# Mega_Shield-v13.net
KiCad netlist of a schematic drawn in EAGLE
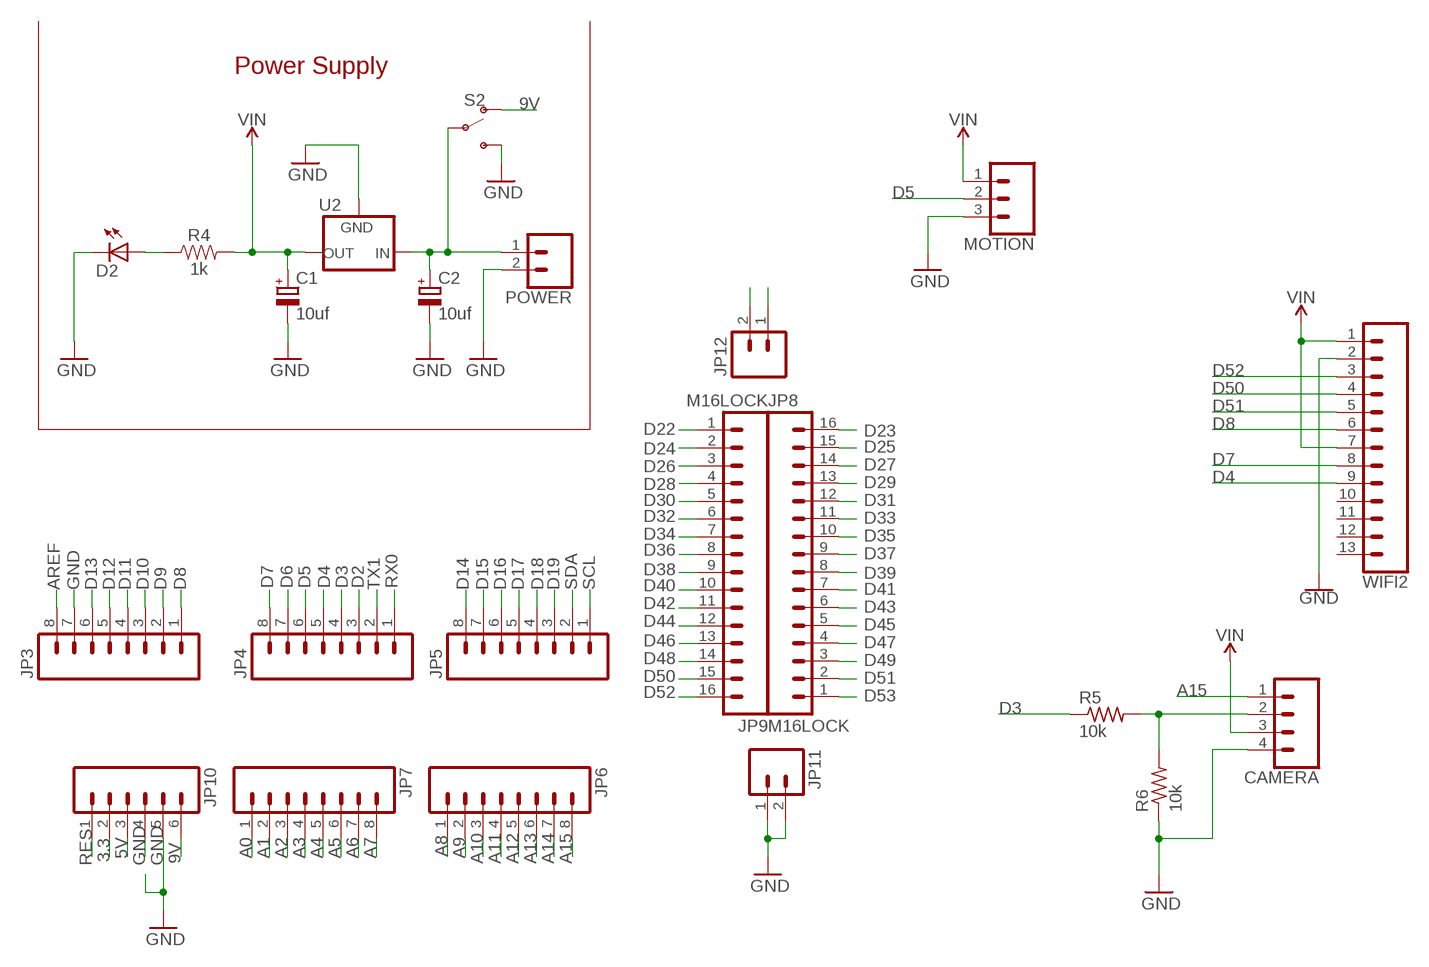
[diagram p0: schematic, sheet 1]

(export (version "E")
  (design (tool "Eeschema 10.0.6"))
  (components
    (comp (ref "C1")
      (value "10uf")
      (footprint "eagle-import:E2,5-6")
      (libsource (lib "eagle-import") (part "CPOL-EUE2.5-6"))
    )
    (comp (ref "C2")
      (value "10uf")
      (footprint "eagle-import:E2,5-6")
      (libsource (lib "eagle-import") (part "CPOL-EUE2.5-6"))
    )
    (comp (ref "CAMERA")
      (value "CONN_04")
      (footprint "eagle-import:1X04")
      (libsource (lib "eagle-import") (part "CONN_04"))
    )
    (comp (ref "D2")
      (value "LED3MM")
      (footprint "eagle-import:LED3MM")
      (libsource (lib "eagle-import") (part "LED3MM"))
    )
    (comp (ref "JP3")
      (value "M08LOCK")
      (footprint "eagle-import:1X08_LOCK")
      (libsource (lib "eagle-import") (part "M08LOCK"))
    )
    (comp (ref "JP4")
      (value "M08LOCK")
      (footprint "eagle-import:1X08_LOCK")
      (libsource (lib "eagle-import") (part "M08LOCK"))
    )
    (comp (ref "JP5")
      (value "M08LOCK")
      (footprint "eagle-import:1X08_LOCK")
      (libsource (lib "eagle-import") (part "M08LOCK"))
    )
    (comp (ref "JP6")
      (value "M08LOCK")
      (footprint "eagle-import:1X08_LOCK")
      (libsource (lib "eagle-import") (part "M08LOCK"))
    )
    (comp (ref "JP7")
      (value "M08LOCK")
      (footprint "eagle-import:1X08_LOCK")
      (libsource (lib "eagle-import") (part "M08LOCK"))
    )
    (comp (ref "JP8")
      (value "M16LOCK")
      (footprint "eagle-import:1X16_LOCK")
      (libsource (lib "eagle-import") (part "M16LOCK"))
    )
    (comp (ref "JP9")
      (value "M16LOCK")
      (footprint "eagle-import:1X16_LOCK")
      (libsource (lib "eagle-import") (part "M16LOCK"))
    )
    (comp (ref "JP10")
      (value "M06LOCK")
      (footprint "eagle-import:1X06_LOCK")
      (libsource (lib "eagle-import") (part "M06LOCK"))
    )
    (comp (ref "JP11")
      (value "M02LOCK")
      (footprint "eagle-import:1X02_LOCK")
      (libsource (lib "eagle-import") (part "M02LOCK"))
    )
    (comp (ref "JP12")
      (value "M02LOCK")
      (footprint "eagle-import:1X02_LOCK")
      (libsource (lib "eagle-import") (part "M02LOCK"))
    )
    (comp (ref "MOTION")
      (value "CONN_03")
      (footprint "eagle-import:1X03")
      (libsource (lib "eagle-import") (part "CONN_03"))
    )
    (comp (ref "POWER")
      (value "CONN_025MM")
      (footprint "eagle-import:SCREWTERMINAL-5MM-2")
      (libsource (lib "eagle-import") (part "CONN_025MM"))
    )
    (comp (ref "R4")
      (value "1k")
      (footprint "eagle-import:AXIAL-0.3")
      (libsource (lib "eagle-import") (part "1KOHM-HORIZ-1/4W-5%"))
    )
    (comp (ref "R5")
      (value "10k")
      (footprint "eagle-import:0207_10")
      (libsource (lib "eagle-import") (part "R-US_0207/10"))
    )
    (comp (ref "R6")
      (value "10k")
      (footprint "eagle-import:0207_10")
      (libsource (lib "eagle-import") (part "R-US_0207/10"))
    )
    (comp (ref "S2")
      (value "SWITCH-SPDT-PTH-11.6X4.0MM")
      (footprint "eagle-import:SWITCH_SPDT_PTH_11.6X4.0MM")
      (libsource (lib "eagle-import") (part "SWITCH-SPDT-PTH-11.6X4.0MM"))
    )
    (comp (ref "U2")
      (value "V_REG_78XX-TO-220")
      (footprint "eagle-import:TO-220-ALT")
      (libsource (lib "eagle-import") (part "V_REG_78XX-TO-220"))
    )
    (comp (ref "WIFI2")
      (value "CONN_13")
      (footprint "eagle-import:1X13")
      (libsource (lib "eagle-import") (part "CONN_13"))
    )
  )
  (nets
    (net (code "1") (name "/3.3") (class "Default")
      (node (ref "JP10") (pin "2") (pinfunction "2_2") (pintype "passive"))
    )
    (net (code "2") (name "/5V") (class "Default")
      (node (ref "JP10") (pin "3") (pinfunction "3_3") (pintype "passive"))
    )
    (net (code "3") (name "/5V@1") (class "Default")
      (node (ref "JP12") (pin "1") (pinfunction "1_1") (pintype "passive"))
      (node (ref "JP12") (pin "2") (pinfunction "2_2") (pintype "passive"))
    )
    (net (code "4") (name "/9V") (class "Default")
      (node (ref "JP10") (pin "6") (pinfunction "6_6") (pintype "passive"))
      (node (ref "S2") (pin "1") (pinfunction "O_1") (pintype "passive"))
    )
    (net (code "5") (name "/A0") (class "Default")
      (node (ref "JP7") (pin "1") (pinfunction "1_1") (pintype "passive"))
    )
    (net (code "6") (name "/A1") (class "Default")
      (node (ref "JP7") (pin "2") (pinfunction "2_2") (pintype "passive"))
    )
    (net (code "7") (name "/A2") (class "Default")
      (node (ref "JP7") (pin "3") (pinfunction "3_3") (pintype "passive"))
    )
    (net (code "8") (name "/A3") (class "Default")
      (node (ref "JP7") (pin "4") (pinfunction "4_4") (pintype "passive"))
    )
    (net (code "9") (name "/A4") (class "Default")
      (node (ref "JP7") (pin "5") (pinfunction "5_5") (pintype "passive"))
    )
    (net (code "10") (name "/A5") (class "Default")
      (node (ref "JP7") (pin "6") (pinfunction "6_6") (pintype "passive"))
    )
    (net (code "11") (name "/A6") (class "Default")
      (node (ref "JP7") (pin "7") (pinfunction "7_7") (pintype "passive"))
    )
    (net (code "12") (name "/A7") (class "Default")
      (node (ref "JP7") (pin "8") (pinfunction "8_8") (pintype "passive"))
    )
    (net (code "13") (name "/A8") (class "Default")
      (node (ref "JP6") (pin "1") (pinfunction "1_1") (pintype "passive"))
    )
    (net (code "14") (name "/A9") (class "Default")
      (node (ref "JP6") (pin "2") (pinfunction "2_2") (pintype "passive"))
    )
    (net (code "15") (name "/A10") (class "Default")
      (node (ref "JP6") (pin "3") (pinfunction "3_3") (pintype "passive"))
    )
    (net (code "16") (name "/A11") (class "Default")
      (node (ref "JP6") (pin "4") (pinfunction "4_4") (pintype "passive"))
    )
    (net (code "17") (name "/A12") (class "Default")
      (node (ref "JP6") (pin "5") (pinfunction "5_5") (pintype "passive"))
    )
    (net (code "18") (name "/A13") (class "Default")
      (node (ref "JP6") (pin "6") (pinfunction "6_6") (pintype "passive"))
    )
    (net (code "19") (name "/A14") (class "Default")
      (node (ref "JP6") (pin "7") (pinfunction "7_7") (pintype "passive"))
    )
    (net (code "20") (name "/A15") (class "Default")
      (node (ref "CAMERA") (pin "1") (pinfunction "1_1") (pintype "passive"))
      (node (ref "JP6") (pin "8") (pinfunction "8_8") (pintype "passive"))
    )
    (net (code "21") (name "/AREF") (class "Default")
      (node (ref "JP3") (pin "8") (pinfunction "8_8") (pintype "passive"))
    )
    (net (code "22") (name "/D2") (class "Default")
      (node (ref "JP4") (pin "3") (pinfunction "3_3") (pintype "passive"))
    )
    (net (code "23") (name "/D3") (class "Default")
      (node (ref "JP4") (pin "4") (pinfunction "4_4") (pintype "passive"))
      (node (ref "R5") (pin "1") (pinfunction "1_1") (pintype "passive"))
    )
    (net (code "24") (name "/D4") (class "Default")
      (node (ref "JP4") (pin "5") (pinfunction "5_5") (pintype "passive"))
      (node (ref "WIFI2") (pin "9") (pinfunction "9_9") (pintype "passive"))
    )
    (net (code "25") (name "/D5") (class "Default")
      (node (ref "JP4") (pin "6") (pinfunction "6_6") (pintype "passive"))
      (node (ref "MOTION") (pin "2") (pinfunction "2_2") (pintype "passive"))
    )
    (net (code "26") (name "/D6") (class "Default")
      (node (ref "JP4") (pin "7") (pinfunction "7_7") (pintype "passive"))
    )
    (net (code "27") (name "/D7") (class "Default")
      (node (ref "JP4") (pin "8") (pinfunction "8_8") (pintype "passive"))
      (node (ref "WIFI2") (pin "8") (pinfunction "8_8") (pintype "passive"))
    )
    (net (code "28") (name "/D8") (class "Default")
      (node (ref "JP3") (pin "1") (pinfunction "1_1") (pintype "passive"))
      (node (ref "WIFI2") (pin "6") (pinfunction "6_6") (pintype "passive"))
    )
    (net (code "29") (name "/D9") (class "Default")
      (node (ref "JP3") (pin "2") (pinfunction "2_2") (pintype "passive"))
    )
    (net (code "30") (name "/D10") (class "Default")
      (node (ref "JP3") (pin "3") (pinfunction "3_3") (pintype "passive"))
    )
    (net (code "31") (name "/D11") (class "Default")
      (node (ref "JP3") (pin "4") (pinfunction "4_4") (pintype "passive"))
    )
    (net (code "32") (name "/D12") (class "Default")
      (node (ref "JP3") (pin "5") (pinfunction "5_5") (pintype "passive"))
    )
    (net (code "33") (name "/D13") (class "Default")
      (node (ref "JP3") (pin "6") (pinfunction "6_6") (pintype "passive"))
    )
    (net (code "34") (name "/D14") (class "Default")
      (node (ref "JP5") (pin "8") (pinfunction "8_8") (pintype "passive"))
    )
    (net (code "35") (name "/D15") (class "Default")
      (node (ref "JP5") (pin "7") (pinfunction "7_7") (pintype "passive"))
    )
    (net (code "36") (name "/D16") (class "Default")
      (node (ref "JP5") (pin "6") (pinfunction "6_6") (pintype "passive"))
    )
    (net (code "37") (name "/D17") (class "Default")
      (node (ref "JP5") (pin "5") (pinfunction "5_5") (pintype "passive"))
    )
    (net (code "38") (name "/D18") (class "Default")
      (node (ref "JP5") (pin "4") (pinfunction "4_4") (pintype "passive"))
    )
    (net (code "39") (name "/D19") (class "Default")
      (node (ref "JP5") (pin "3") (pinfunction "3_3") (pintype "passive"))
    )
    (net (code "40") (name "/D22") (class "Default")
      (node (ref "JP9") (pin "1") (pinfunction "1_1") (pintype "passive"))
    )
    (net (code "41") (name "/D23") (class "Default")
      (node (ref "JP8") (pin "16") (pinfunction "16_16") (pintype "passive"))
    )
    (net (code "42") (name "/D24") (class "Default")
      (node (ref "JP9") (pin "2") (pinfunction "2_2") (pintype "passive"))
    )
    (net (code "43") (name "/D25") (class "Default")
      (node (ref "JP8") (pin "15") (pinfunction "15_15") (pintype "passive"))
    )
    (net (code "44") (name "/D26") (class "Default")
      (node (ref "JP9") (pin "3") (pinfunction "3_3") (pintype "passive"))
    )
    (net (code "45") (name "/D27") (class "Default")
      (node (ref "JP8") (pin "14") (pinfunction "14_14") (pintype "passive"))
    )
    (net (code "46") (name "/D28") (class "Default")
      (node (ref "JP9") (pin "4") (pinfunction "4_4") (pintype "passive"))
    )
    (net (code "47") (name "/D29") (class "Default")
      (node (ref "JP8") (pin "13") (pinfunction "13_13") (pintype "passive"))
    )
    (net (code "48") (name "/D30") (class "Default")
      (node (ref "JP9") (pin "5") (pinfunction "5_5") (pintype "passive"))
    )
    (net (code "49") (name "/D31") (class "Default")
      (node (ref "JP8") (pin "12") (pinfunction "12_12") (pintype "passive"))
    )
    (net (code "50") (name "/D32") (class "Default")
      (node (ref "JP9") (pin "6") (pinfunction "6_6") (pintype "passive"))
    )
    (net (code "51") (name "/D33") (class "Default")
      (node (ref "JP8") (pin "11") (pinfunction "11_11") (pintype "passive"))
    )
    (net (code "52") (name "/D34") (class "Default")
      (node (ref "JP9") (pin "7") (pinfunction "7_7") (pintype "passive"))
    )
    (net (code "53") (name "/D35") (class "Default")
      (node (ref "JP8") (pin "10") (pinfunction "10_10") (pintype "passive"))
    )
    (net (code "54") (name "/D36") (class "Default")
      (node (ref "JP9") (pin "8") (pinfunction "8_8") (pintype "passive"))
    )
    (net (code "55") (name "/D37") (class "Default")
      (node (ref "JP8") (pin "9") (pinfunction "9_9") (pintype "passive"))
    )
    (net (code "56") (name "/D38") (class "Default")
      (node (ref "JP9") (pin "9") (pinfunction "9_9") (pintype "passive"))
    )
    (net (code "57") (name "/D39") (class "Default")
      (node (ref "JP8") (pin "8") (pinfunction "8_8") (pintype "passive"))
    )
    (net (code "58") (name "/D40") (class "Default")
      (node (ref "JP9") (pin "10") (pinfunction "10_10") (pintype "passive"))
    )
    (net (code "59") (name "/D41") (class "Default")
      (node (ref "JP8") (pin "7") (pinfunction "7_7") (pintype "passive"))
    )
    (net (code "60") (name "/D42") (class "Default")
      (node (ref "JP9") (pin "11") (pinfunction "11_11") (pintype "passive"))
    )
    (net (code "61") (name "/D43") (class "Default")
      (node (ref "JP8") (pin "6") (pinfunction "6_6") (pintype "passive"))
    )
    (net (code "62") (name "/D44") (class "Default")
      (node (ref "JP9") (pin "12") (pinfunction "12_12") (pintype "passive"))
    )
    (net (code "63") (name "/D45") (class "Default")
      (node (ref "JP8") (pin "5") (pinfunction "5_5") (pintype "passive"))
    )
    (net (code "64") (name "/D46") (class "Default")
      (node (ref "JP9") (pin "13") (pinfunction "13_13") (pintype "passive"))
    )
    (net (code "65") (name "/D47") (class "Default")
      (node (ref "JP8") (pin "4") (pinfunction "4_4") (pintype "passive"))
    )
    (net (code "66") (name "/D48") (class "Default")
      (node (ref "JP9") (pin "14") (pinfunction "14_14") (pintype "passive"))
    )
    (net (code "67") (name "/D49") (class "Default")
      (node (ref "JP8") (pin "3") (pinfunction "3_3") (pintype "passive"))
    )
    (net (code "68") (name "/D50") (class "Default")
      (node (ref "JP9") (pin "15") (pinfunction "15_15") (pintype "passive"))
      (node (ref "WIFI2") (pin "4") (pinfunction "4_4") (pintype "passive"))
    )
    (net (code "69") (name "/D51") (class "Default")
      (node (ref "JP8") (pin "2") (pinfunction "2_2") (pintype "passive"))
      (node (ref "WIFI2") (pin "5") (pinfunction "5_5") (pintype "passive"))
    )
    (net (code "70") (name "/D52") (class "Default")
      (node (ref "JP9") (pin "16") (pinfunction "16_16") (pintype "passive"))
      (node (ref "WIFI2") (pin "3") (pinfunction "3_3") (pintype "passive"))
    )
    (net (code "71") (name "/D53") (class "Default")
      (node (ref "JP8") (pin "1") (pinfunction "1_1") (pintype "passive"))
    )
    (net (code "72") (name "/RES") (class "Default")
      (node (ref "JP10") (pin "1") (pinfunction "1_1") (pintype "passive"))
    )
    (net (code "73") (name "/RX0") (class "Default")
      (node (ref "JP4") (pin "1") (pinfunction "1_1") (pintype "passive"))
    )
    (net (code "74") (name "/SCL") (class "Default")
      (node (ref "JP5") (pin "1") (pinfunction "1_1") (pintype "passive"))
    )
    (net (code "75") (name "/SDA") (class "Default")
      (node (ref "JP5") (pin "2") (pinfunction "2_2") (pintype "passive"))
    )
    (net (code "76") (name "/TX1") (class "Default")
      (node (ref "JP4") (pin "2") (pinfunction "2_2") (pintype "passive"))
    )
    (net (code "77") (name "GND") (class "Default")
      (node (ref "C1") (pin "-") (pinfunction "-_-") (pintype "passive"))
      (node (ref "C2") (pin "-") (pinfunction "-_-") (pintype "passive"))
      (node (ref "CAMERA") (pin "4") (pinfunction "4_4") (pintype "passive"))
      (node (ref "D2") (pin "K") (pinfunction "C_K") (pintype "passive"))
      (node (ref "JP10") (pin "4") (pinfunction "4_4") (pintype "passive"))
      (node (ref "JP10") (pin "5") (pinfunction "5_5") (pintype "passive"))
      (node (ref "JP11") (pin "1") (pinfunction "1_1") (pintype "passive"))
      (node (ref "JP11") (pin "2") (pinfunction "2_2") (pintype "passive"))
      (node (ref "JP3") (pin "7") (pinfunction "7_7") (pintype "passive"))
      (node (ref "MOTION") (pin "3") (pinfunction "3_3") (pintype "passive"))
      (node (ref "POWER") (pin "2") (pinfunction "2_2") (pintype "passive"))
      (node (ref "R6") (pin "1") (pinfunction "1_1") (pintype "passive"))
      (node (ref "S2") (pin "3") (pinfunction "S_3") (pintype "passive"))
      (node (ref "U2") (pin "GND") (pinfunction "GND_GND") (pintype "input"))
      (node (ref "WIFI2") (pin "2") (pinfunction "2_2") (pintype "passive"))
    )
    (net (code "78") (name "Net-(CAMERA-Pad2)") (class "Default")
      (node (ref "CAMERA") (pin "2") (pinfunction "2_2") (pintype "passive"))
      (node (ref "R5") (pin "2") (pinfunction "2_2") (pintype "passive"))
      (node (ref "R6") (pin "2") (pinfunction "2_2") (pintype "passive"))
    )
    (net (code "79") (name "Net-(R4-1)") (class "Default")
      (node (ref "D2") (pin "A") (pinfunction "A_A") (pintype "passive"))
      (node (ref "R4") (pin "P$1") (pinfunction "1_P$1") (pintype "passive"))
    )
    (net (code "80") (name "Net-(S2-P)") (class "Default")
      (node (ref "C2") (pin "+") (pinfunction "+_+") (pintype "passive"))
      (node (ref "POWER") (pin "1") (pinfunction "1_1") (pintype "passive"))
      (node (ref "S2") (pin "2") (pinfunction "P_2") (pintype "passive"))
      (node (ref "U2") (pin "IN") (pinfunction "IN_IN") (pintype "input"))
    )
    (net (code "81") (name "VIN") (class "Default")
      (node (ref "C1") (pin "+") (pinfunction "+_+") (pintype "passive"))
      (node (ref "CAMERA") (pin "3") (pinfunction "3_3") (pintype "passive"))
      (node (ref "MOTION") (pin "1") (pinfunction "1_1") (pintype "passive"))
      (node (ref "R4") (pin "P$2") (pinfunction "2_P$2") (pintype "passive"))
      (node (ref "U2") (pin "OUT") (pinfunction "OUT_OUT") (pintype "passive"))
      (node (ref "WIFI2") (pin "1") (pinfunction "1_1") (pintype "passive"))
      (node (ref "WIFI2") (pin "7") (pinfunction "7_7") (pintype "passive"))
    )
    (net (code "82") (name "unconnected-(WIFI2-Pad10)") (class "Default")
      (node (ref "WIFI2") (pin "10") (pinfunction "10_10") (pintype "passive"))
    )
    (net (code "83") (name "unconnected-(WIFI2-Pad11)") (class "Default")
      (node (ref "WIFI2") (pin "11") (pinfunction "11_11") (pintype "passive"))
    )
    (net (code "84") (name "unconnected-(WIFI2-Pad12)") (class "Default")
      (node (ref "WIFI2") (pin "12") (pinfunction "12_12") (pintype "passive"))
    )
    (net (code "85") (name "unconnected-(WIFI2-Pad13)") (class "Default")
      (node (ref "WIFI2") (pin "13") (pinfunction "13_13") (pintype "passive"))
    )
  )
)
